# Power_Converter_12V_as_TO-3_replacement.net
KiCad netlist of a schematic drawn in Altium Designer
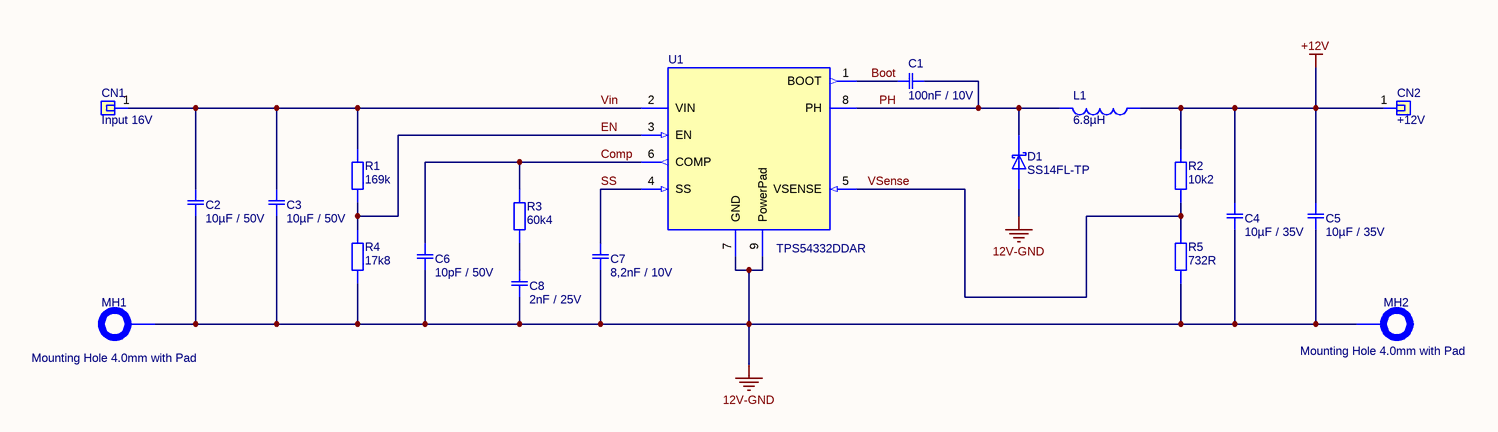
[diagram p0: Power Converter 12V as TO-3 replacement.SchDoc]

(export (version "E")
  (design (tool "Eeschema 10.0.6"))
  (components
    (comp (ref "C1")
      (value "100nF / 10V")
      (footprint "CAP CER SMD 0402 100nF 10V Murata GRM155R71A104KA01D")
      (description "CAP CER 0.1UF 10V X7R 0402")
      (fields (field (name "VOLTAGE") "10V") (field (name "TOLERANCE") "10%"))
      (libsource (lib "PCB-Tech Cloud") (part "Capacitor"))
    )
    (comp (ref "C2")
      (value "10µF / 50V")
      (footprint "CAP SMD 10µF 50V 1210 TDK C3225X7R1H106M250AC")
      (description "TDK - C3225X7R1H106M250AC - C3225X7R1H106MT000E")
      (fields (field (name "TOLERANCE") "20%"))
      (libsource (lib "PCB-Tech Cloud") (part "Capacitor"))
    )
    (comp (ref "C3")
      (value "10µF / 50V")
      (footprint "CAP SMD 10µF 50V 1210 TDK C3225X7R1H106M250AC")
      (description "TDK - C3225X7R1H106M250AC - C3225X7R1H106MT000E")
      (fields (field (name "TOLERANCE") "20%"))
      (libsource (lib "PCB-Tech Cloud") (part "Capacitor"))
    )
    (comp (ref "C4")
      (value "10µF / 35V")
      (footprint "CAP SMD 10µF 50V 1210 TDK C3216X6S1V106K160AC")
      (description "Cap Ceramic 10uF 35V X6S 10% SMD 1206 105°C Punched Paper T/R")
      (fields (field (name "TOLERANCE") "10%"))
      (libsource (lib "PCB-Tech Cloud") (part "Capacitor"))
    )
    (comp (ref "C5")
      (value "10µF / 35V")
      (footprint "CAP SMD 10µF 50V 1210 TDK C3216X6S1V106K160AC")
      (description "Cap Ceramic 10uF 35V X6S 10% SMD 1206 105°C Punched Paper T/R")
      (fields (field (name "TOLERANCE") "10%"))
      (libsource (lib "PCB-Tech Cloud") (part "Capacitor"))
    )
    (comp (ref "C6")
      (value "10pF / 50V")
      (footprint "CAP CER SMD 0805 10pF 50V Samsung CL21C100JBANNNC")
      (description "Cap Ceramic 10pF 50VDC C0G 5% SMD 0805 Paper T/R")
      (fields (field (name "TOLERANCE") "5%"))
      (libsource (lib "PCB-Tech Cloud") (part "Capacitor"))
    )
    (comp (ref "C7")
      (value "8,2nF / 10V")
      (footprint "CAP CER SMD 0201 8,2nF 10V Murata GRM033R71A822KA01D")
      (description "Multilayer Ceramic Capacitors MLCC - SMD/SMT 0.0082uF 10volts 10%")
      (fields (field (name "TOLERANCE") "10%"))
      (libsource (lib "PCB-Tech Cloud") (part "Capacitor"))
    )
    (comp (ref "C8")
      (value "2nF / 25V")
      (footprint "CAP CER SMD 0805 2nF 25V Kemet C0805C202J3GACTU")
      (description "Multilayer Ceramic Capacitors MLCC - SMD/SMT 25volts 2000pF C0G 5%")
      (fields (field (name "TOLERANCE") "5%"))
      (libsource (lib "PCB-Tech Cloud") (part "Capacitor"))
    )
    (comp (ref "CN1")
      (value "Input 16V")
      (footprint "Printed Circuit Pin 1.02mm 3125-2-00-80-00-00-08-0")
      (description "CONN PC PIN CIRC 0.040DIA TIN")
      (libsource (lib "") (part "CONN 01x01_1"))
    )
    (comp (ref "CN2")
      (value "+12V")
      (footprint "Printed Circuit Pin 1.02mm 3125-2-00-80-00-00-08-0")
      (description "CONN PC PIN CIRC 0.040DIA TIN")
      (libsource (lib "PCB-Tech Cloud") (part "CONN 01x01"))
    )
    (comp (ref "D1")
      (value "SS14FL-TP")
      (footprint "SS14FL")
      (description "DIODE SCHOTTKY 40V 1A DO221AC")
      (libsource (lib "PCB-Tech Cloud") (part "Schottky Diode"))
    )
    (comp (ref "L1")
      (value "6.8µH")
      (footprint "Shielded Drum Core 6.8µH TDK B82464G4682M")
      (description "Inductor Power Shielded Wirewound 6.8uH 20% 100KHz Ferrite 4.3A 0.02Ohm DCR Automotive T/R")
      (fields (field (name "TOLERANCE") "20%"))
      (libsource (lib "PCB-Tech Cloud") (part "Inductor Standard"))
    )
    (comp (ref "MH1")
      (value "Mounting Hole 4.0mm with Pad")
      (footprint "Mounting Hole 4mm with Pad")
      (libsource (lib "PCB-Tech Cloud") (part "Mounting Hole with Pad"))
    )
    (comp (ref "MH2")
      (value "Mounting Hole 4.0mm with Pad")
      (footprint "Mounting Hole 4mm with Pad")
      (libsource (lib "PCB-Tech Cloud") (part "Mounting Hole with Pad"))
    )
    (comp (ref "R1")
      (value "169k")
      (footprint "RES SMD 0402 169k Vishay CRCW0402169KFKED")
      (description "VISHAY - CRCW0402169KFKED - RES, THICK FILM, 169K, 1%, 0.063W, 0402, REEL")
      (fields (field (name "TOLERANCE") "1%"))
      (libsource (lib "PCB-Tech Cloud") (part "Resistor"))
    )
    (comp (ref "R2")
      (value "10k2")
      (footprint "RES SMD 0402 10k2 Vishay CRCW040210K2FKED")
      (fields (field (name "TOLERANCE") "1%"))
      (libsource (lib "PCB-Tech Cloud") (part "Resistor"))
    )
    (comp (ref "R3")
      (value "60k4")
      (footprint "RES SMD 0402 60k4 Vishay CRCW040260K4FKED")
      (fields (field (name "TOLERANCE") "1%"))
      (libsource (lib "PCB-Tech Cloud") (part "Resistor"))
    )
    (comp (ref "R4")
      (value "17k8")
      (footprint "RES SMD 0402 17k8 Vishay CRCW040217K8FKED")
      (description "VISHAY - CRCW040217K8FKED - RES, THICK FILM, 17K8, 1%, 0.063W, 0402")
      (fields (field (name "TOLERANCE") "1%"))
      (libsource (lib "PCB-Tech Cloud") (part "Resistor"))
    )
    (comp (ref "R5")
      (value "732R")
      (footprint "RES SMD 0402 732R Vishay CRCW0402732RFKED")
      (fields (field (name "TOLERANCE") "1%"))
      (libsource (lib "PCB-Tech Cloud") (part "Resistor"))
    )
    (comp (ref "U1")
      (value "TPS54332DDAR")
      (footprint "DC-DC Converter (Buck) TPS54332DDAR SO-Power Pad")
      (description "TEXAS INSTRUMENTS - TPS54332DDAR - DC/DC CONV, BUCK, 1MHZ, SOIC-8")
      (libsource (lib "PCB-Tech Cloud") (part "DC-DC Converter (Buck) TPS54332DDAR SO-Power Pad"))
    )
  )
  (nets
    (net (code "1") (name "+12V") (class "Default")
      (node (ref "C4") (pin "2") (pinfunction "2_2") (pintype "passive"))
      (node (ref "C5") (pin "2") (pinfunction "2_2") (pintype "passive"))
      (node (ref "CN2") (pin "1") (pinfunction "1_1") (pintype "passive"))
      (node (ref "L1") (pin "2") (pinfunction "2_2") (pintype "passive"))
      (node (ref "R2") (pin "2") (pinfunction "2_2") (pintype "passive"))
    )
    (net (code "2") (name "/Boot") (class "Default")
      (node (ref "C1") (pin "1") (pinfunction "1_1") (pintype "passive"))
      (node (ref "U1") (pin "1") (pinfunction "BOOT_1") (pintype "output"))
    )
    (net (code "3") (name "/Comp") (class "Default")
      (node (ref "C6") (pin "2") (pinfunction "2_2") (pintype "passive"))
      (node (ref "R3") (pin "2") (pinfunction "2_2") (pintype "passive"))
      (node (ref "U1") (pin "6") (pinfunction "COMP_6") (pintype "output"))
    )
    (net (code "4") (name "/EN") (class "Default")
      (node (ref "R1") (pin "1") (pinfunction "1_1") (pintype "passive"))
      (node (ref "R4") (pin "2") (pinfunction "2_2") (pintype "passive"))
      (node (ref "U1") (pin "3") (pinfunction "EN_3") (pintype "input"))
    )
    (net (code "5") (name "/PH") (class "Default")
      (node (ref "C1") (pin "2") (pinfunction "2_2") (pintype "passive"))
      (node (ref "D1") (pin "1") (pinfunction "1_1") (pintype "passive"))
      (node (ref "L1") (pin "1") (pinfunction "1_1") (pintype "passive"))
      (node (ref "U1") (pin "8") (pinfunction "PH_8") (pintype "power_in"))
    )
    (net (code "6") (name "/SS") (class "Default")
      (node (ref "C7") (pin "2") (pinfunction "2_2") (pintype "passive"))
      (node (ref "U1") (pin "4") (pinfunction "SS_4") (pintype "input"))
    )
    (net (code "7") (name "/VSense") (class "Default")
      (node (ref "R2") (pin "1") (pinfunction "1_1") (pintype "passive"))
      (node (ref "R5") (pin "2") (pinfunction "2_2") (pintype "passive"))
      (node (ref "U1") (pin "5") (pinfunction "VSENSE_5") (pintype "input"))
    )
    (net (code "8") (name "/Vin") (class "Default")
      (node (ref "C2") (pin "2") (pinfunction "2_2") (pintype "passive"))
      (node (ref "C3") (pin "2") (pinfunction "2_2") (pintype "passive"))
      (node (ref "CN1") (pin "1") (pinfunction "1_1") (pintype "passive"))
      (node (ref "R1") (pin "2") (pinfunction "2_2") (pintype "passive"))
      (node (ref "U1") (pin "2") (pinfunction "VIN_2") (pintype "power_in"))
    )
    (net (code "9") (name "12V-GND") (class "Default")
      (node (ref "C2") (pin "1") (pinfunction "1_1") (pintype "passive"))
      (node (ref "C3") (pin "1") (pinfunction "1_1") (pintype "passive"))
      (node (ref "C4") (pin "1") (pinfunction "1_1") (pintype "passive"))
      (node (ref "C5") (pin "1") (pinfunction "1_1") (pintype "passive"))
      (node (ref "C6") (pin "1") (pinfunction "1_1") (pintype "passive"))
      (node (ref "C7") (pin "1") (pinfunction "1_1") (pintype "passive"))
      (node (ref "C8") (pin "2") (pinfunction "2_2") (pintype "passive"))
      (node (ref "D1") (pin "2") (pinfunction "2_2") (pintype "passive"))
      (node (ref "MH1") (pin "1") (pinfunction "1_1") (pintype "power_in"))
      (node (ref "MH2") (pin "1") (pinfunction "1_1") (pintype "power_in"))
      (node (ref "R4") (pin "1") (pinfunction "1_1") (pintype "passive"))
      (node (ref "R5") (pin "1") (pinfunction "1_1") (pintype "passive"))
      (node (ref "U1") (pin "7") (pinfunction "GND_7") (pintype "power_in"))
      (node (ref "U1") (pin "9") (pinfunction "PowerPad_9") (pintype "power_in"))
    )
    (net (code "10") (name "Net-(C8-Pad1)") (class "Default")
      (node (ref "C8") (pin "1") (pinfunction "1_1") (pintype "passive"))
      (node (ref "R3") (pin "1") (pinfunction "1_1") (pintype "passive"))
    )
  )
)
